# Board.net
KiCad netlist of a schematic drawn in Altium Designer
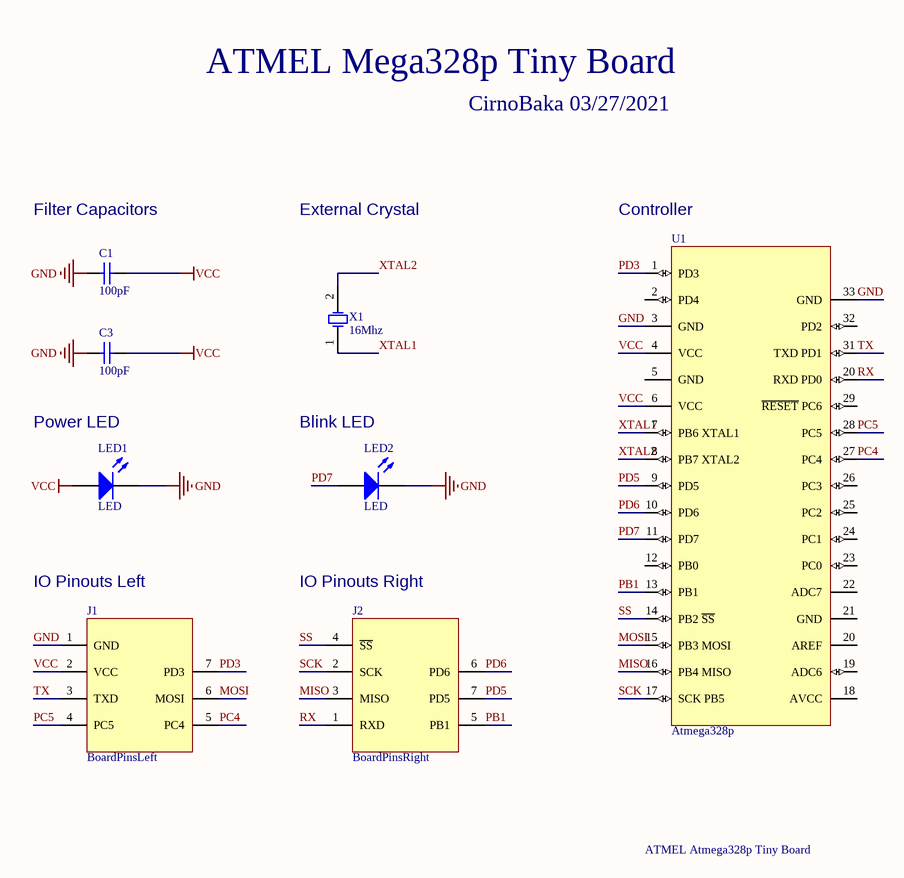
[diagram p0: Board.SchDoc]

(export (version "E")
  (design (tool "Eeschema 10.0.6"))
  (components
    (comp (ref "C1") (value "100pF") (footprint "C0402") (libsource (lib "Board") (part "Capacitor")))
    (comp (ref "C3") (value "100pF") (footprint "C0402") (libsource (lib "Board") (part "Capacitor")))
    (comp (ref "J1")
      (value "BoardPinsLeft")
      (footprint "Connector7G")
      (libsource (lib "Board") (part "BoardPinsLeft"))
    )
    (comp (ref "J2")
      (value "BoardPinsRight")
      (footprint "Connector7")
      (libsource (lib "Board") (part "BoardPinsRight"))
    )
    (comp (ref "LED1") (value "LED") (footprint "LED0402") (libsource (lib "Board") (part "LED")))
    (comp (ref "LED2") (value "LED") (footprint "LED0402") (libsource (lib "Board") (part "LED")))
    (comp (ref "U1")
      (value "Atmega328p")
      (footprint "Atmega328p")
      (libsource (lib "Board") (part "Atmega328p"))
    )
    (comp (ref "X1") (value "16Mhz") (footprint "CSTCE16M0V53-RO") (libsource (lib "Board") (part "Crystal")))
  )
  (nets
    (net (code "1") (name "/MISO") (class "Default")
      (node (ref "J2") (pin "3") (pinfunction "MISO_3") (pintype "passive"))
      (node (ref "U1") (pin "16") (pinfunction "PB4_MISO_16") (pintype "bidirectional"))
    )
    (net (code "2") (name "/MOSI") (class "Default")
      (node (ref "J1") (pin "6") (pinfunction "MOSI_6") (pintype "passive"))
      (node (ref "U1") (pin "15") (pinfunction "PB3_MOSI_15") (pintype "bidirectional"))
    )
    (net (code "3") (name "/PB1") (class "Default")
      (node (ref "J2") (pin "5") (pinfunction "PB1_5") (pintype "passive"))
      (node (ref "U1") (pin "13") (pinfunction "PB1_13") (pintype "bidirectional"))
    )
    (net (code "4") (name "/PC4") (class "Default")
      (node (ref "J1") (pin "5") (pinfunction "PC4_5") (pintype "passive"))
      (node (ref "U1") (pin "27") (pinfunction "PC4_27") (pintype "bidirectional"))
    )
    (net (code "5") (name "/PC5") (class "Default")
      (node (ref "J1") (pin "4") (pinfunction "PC5_4") (pintype "passive"))
      (node (ref "U1") (pin "28") (pinfunction "PC5_28") (pintype "bidirectional"))
    )
    (net (code "6") (name "/PD3") (class "Default")
      (node (ref "J1") (pin "7") (pinfunction "PD3_7") (pintype "passive"))
      (node (ref "U1") (pin "1") (pinfunction "PD3_1") (pintype "bidirectional"))
    )
    (net (code "7") (name "/PD5") (class "Default")
      (node (ref "J2") (pin "7") (pinfunction "PD5_7") (pintype "passive"))
      (node (ref "U1") (pin "9") (pinfunction "PD5_9") (pintype "bidirectional"))
    )
    (net (code "8") (name "/PD6") (class "Default")
      (node (ref "J2") (pin "6") (pinfunction "PD6_6") (pintype "passive"))
      (node (ref "U1") (pin "10") (pinfunction "PD6_10") (pintype "bidirectional"))
    )
    (net (code "9") (name "/PD7") (class "Default")
      (node (ref "LED2") (pin "1") (pinfunction "A_1") (pintype "passive"))
      (node (ref "U1") (pin "11") (pinfunction "PD7_11") (pintype "bidirectional"))
    )
    (net (code "10") (name "/RX") (class "Default")
      (node (ref "J2") (pin "1") (pinfunction "RXD_1") (pintype "passive"))
      (node (ref "U1") (pin "20") (pinfunction "RXD_PD0_20") (pintype "bidirectional"))
    )
    (net (code "11") (name "/SCK") (class "Default")
      (node (ref "J2") (pin "2") (pinfunction "SCK_2") (pintype "passive"))
      (node (ref "U1") (pin "17") (pinfunction "SCK_PB5_17") (pintype "bidirectional"))
    )
    (net (code "12") (name "/SS") (class "Default")
      (node (ref "J2") (pin "4") (pinfunction "~{SS}_4") (pintype "passive"))
      (node (ref "U1") (pin "14") (pinfunction "PB2_~{SS}_14") (pintype "bidirectional"))
    )
    (net (code "13") (name "/TX") (class "Default")
      (node (ref "J1") (pin "3") (pinfunction "TXD_3") (pintype "passive"))
      (node (ref "U1") (pin "31") (pinfunction "TXD_PD1_31") (pintype "bidirectional"))
    )
    (net (code "14") (name "/XTAL1") (class "Default")
      (node (ref "U1") (pin "7") (pinfunction "PB6_XTAL1_7") (pintype "bidirectional"))
      (node (ref "X1") (pin "1") (pinfunction "OSC1_1") (pintype "passive"))
    )
    (net (code "15") (name "/XTAL2") (class "Default")
      (node (ref "U1") (pin "8") (pinfunction "PB7_XTAL2_8") (pintype "bidirectional"))
      (node (ref "X1") (pin "2") (pinfunction "OSC2_2") (pintype "passive"))
    )
    (net (code "16") (name "GND") (class "Default")
      (node (ref "C1") (pin "1") (pinfunction "1_1") (pintype "passive"))
      (node (ref "C3") (pin "1") (pinfunction "1_1") (pintype "passive"))
      (node (ref "J1") (pin "1") (pinfunction "GND_1") (pintype "passive"))
      (node (ref "LED1") (pin "2") (pinfunction "K_2") (pintype "passive"))
      (node (ref "LED2") (pin "2") (pinfunction "K_2") (pintype "passive"))
      (node (ref "U1") (pin "3") (pinfunction "GND_3") (pintype "passive"))
      (node (ref "U1") (pin "33") (pinfunction "GND_33") (pintype "passive"))
    )
    (net (code "17") (name "VCC") (class "Default")
      (node (ref "C1") (pin "2") (pinfunction "2_2") (pintype "passive"))
      (node (ref "C3") (pin "2") (pinfunction "2_2") (pintype "passive"))
      (node (ref "J1") (pin "2") (pinfunction "VCC_2") (pintype "passive"))
      (node (ref "LED1") (pin "1") (pinfunction "A_1") (pintype "passive"))
      (node (ref "U1") (pin "4") (pinfunction "VCC_4") (pintype "passive"))
      (node (ref "U1") (pin "6") (pinfunction "VCC_6") (pintype "passive"))
    )
    (net (code "18") (name "unconnected-(U1-ADC6-Pad19)") (class "Default")
      (node (ref "U1") (pin "19") (pinfunction "ADC6_19") (pintype "bidirectional"))
    )
    (net (code "19") (name "unconnected-(U1-ADC7-Pad22)") (class "Default")
      (node (ref "U1") (pin "22") (pinfunction "ADC7_22") (pintype "passive"))
    )
    (net (code "20") (name "unconnected-(U1-AREF-Pad20)") (class "Default")
      (node (ref "U1") (pin "20") (pinfunction "AREF_20") (pintype "passive"))
    )
    (net (code "21") (name "unconnected-(U1-AVCC-Pad18)") (class "Default")
      (node (ref "U1") (pin "18") (pinfunction "AVCC_18") (pintype "passive"))
    )
    (net (code "22") (name "unconnected-(U1-GND-Pad5)") (class "Default")
      (node (ref "U1") (pin "5") (pinfunction "GND_5") (pintype "passive"))
    )
    (net (code "23") (name "unconnected-(U1-GND-Pad21)") (class "Default")
      (node (ref "U1") (pin "21") (pinfunction "GND_21") (pintype "passive"))
    )
    (net (code "24") (name "unconnected-(U1-PB0-Pad12)") (class "Default")
      (node (ref "U1") (pin "12") (pinfunction "PB0_12") (pintype "bidirectional"))
    )
    (net (code "25") (name "unconnected-(U1-PC0-Pad23)") (class "Default")
      (node (ref "U1") (pin "23") (pinfunction "PC0_23") (pintype "bidirectional"))
    )
    (net (code "26") (name "unconnected-(U1-PC1-Pad24)") (class "Default")
      (node (ref "U1") (pin "24") (pinfunction "PC1_24") (pintype "bidirectional"))
    )
    (net (code "27") (name "unconnected-(U1-PC2-Pad25)") (class "Default")
      (node (ref "U1") (pin "25") (pinfunction "PC2_25") (pintype "bidirectional"))
    )
    (net (code "28") (name "unconnected-(U1-PC3-Pad26)") (class "Default")
      (node (ref "U1") (pin "26") (pinfunction "PC3_26") (pintype "bidirectional"))
    )
    (net (code "29") (name "unconnected-(U1-PD2-Pad32)") (class "Default")
      (node (ref "U1") (pin "32") (pinfunction "PD2_32") (pintype "bidirectional"))
    )
    (net (code "30") (name "unconnected-(U1-PD4-Pad2)") (class "Default")
      (node (ref "U1") (pin "2") (pinfunction "PD4_2") (pintype "bidirectional"))
    )
    (net (code "31") (name "unconnected-(U1-~{RESET}_PC6-Pad29)") (class "Default")
      (node (ref "U1") (pin "29") (pinfunction "~{RESET}_PC6_29") (pintype "bidirectional"))
    )
  )
)
